# programmer-smd.net
KiCad netlist of a schematic drawn in EAGLE
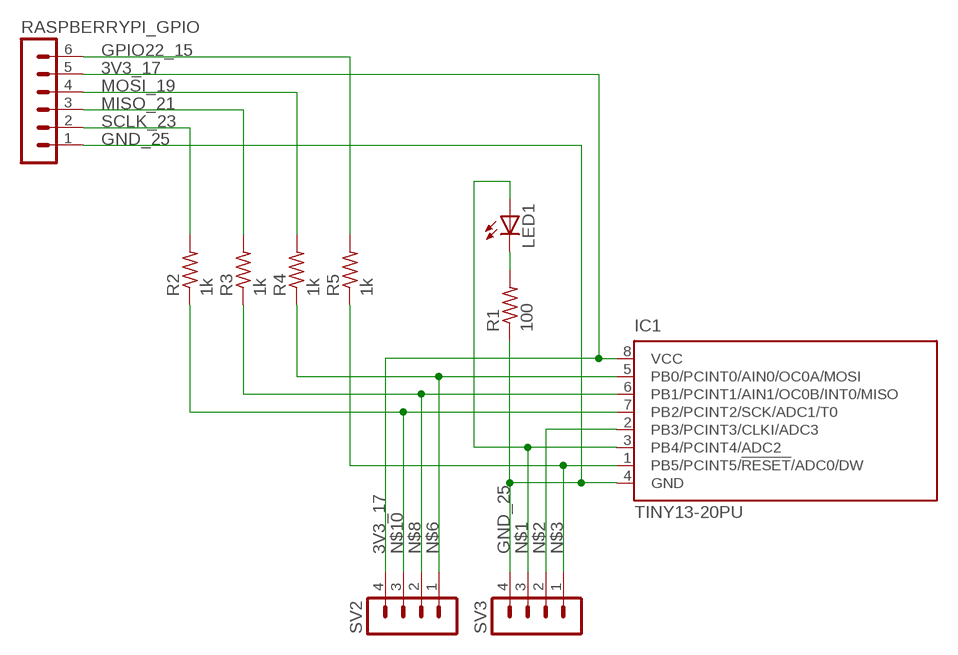
[diagram p0: schematic, sheet 1]

(export (version "E")
  (design (tool "Eeschema 10.0.6"))
  (components
    (comp (ref "IC1")
      (value "TINY13-20PU")
      (footprint "eagle-import:DIL08")
      (fields (field (name "MPN") "ATTINY13-20PU"))
      (libsource (lib "eagle-import") (part "TINY13PU-20"))
    )
    (comp (ref "LED1")
      (value "LEDCHIP-LED0805")
      (footprint "eagle-import:CHIP-LED0805")
      (libsource (lib "eagle-import") (part "LEDCHIP-LED0805"))
    )
    (comp (ref "R1")
      (value "100")
      (footprint "eagle-import:M0805")
      (libsource (lib "eagle-import") (part "R-US_M0805"))
    )
    (comp (ref "R2")
      (value "1k")
      (footprint "eagle-import:M0805")
      (libsource (lib "eagle-import") (part "R-US_M0805"))
    )
    (comp (ref "R3")
      (value "1k")
      (footprint "eagle-import:M0805")
      (libsource (lib "eagle-import") (part "R-US_M0805"))
    )
    (comp (ref "R4")
      (value "1k")
      (footprint "eagle-import:M0805")
      (libsource (lib "eagle-import") (part "R-US_M0805"))
    )
    (comp (ref "R5")
      (value "1k")
      (footprint "eagle-import:M0805")
      (libsource (lib "eagle-import") (part "R-US_M0805"))
    )
    (comp (ref "RASPBERRYPI_GPIO")
      (value "MA06-1")
      (footprint "eagle-import:MA06-1")
      (libsource (lib "eagle-import") (part "MA06-1"))
    )
    (comp (ref "SV2")
      (value "MA04-1")
      (footprint "eagle-import:MA04-1")
      (libsource (lib "eagle-import") (part "MA04-1"))
    )
    (comp (ref "SV3")
      (value "MA04-1")
      (footprint "eagle-import:MA04-1")
      (libsource (lib "eagle-import") (part "MA04-1"))
    )
  )
  (nets
    (net (code "1") (name "/3V3_17") (class "Default")
      (node (ref "IC1") (pin "8") (pinfunction "VCC_8") (pintype "power_in"))
      (node (ref "RASPBERRYPI_GPIO") (pin "5") (pinfunction "5_5") (pintype "passive"))
      (node (ref "SV2") (pin "4") (pinfunction "4_4") (pintype "passive"))
    )
    (net (code "2") (name "/GND_25") (class "Default")
      (node (ref "IC1") (pin "4") (pinfunction "GND_4") (pintype "power_in"))
      (node (ref "R1") (pin "1") (pinfunction "1_1") (pintype "passive"))
      (node (ref "RASPBERRYPI_GPIO") (pin "1") (pinfunction "1_1") (pintype "passive"))
      (node (ref "SV3") (pin "4") (pinfunction "4_4") (pintype "passive"))
    )
    (net (code "3") (name "/GPIO22_15") (class "Default")
      (node (ref "R5") (pin "2") (pinfunction "2_2") (pintype "passive"))
      (node (ref "RASPBERRYPI_GPIO") (pin "6") (pinfunction "6_6") (pintype "passive"))
    )
    (net (code "4") (name "/MISO_21") (class "Default")
      (node (ref "R3") (pin "2") (pinfunction "2_2") (pintype "passive"))
      (node (ref "RASPBERRYPI_GPIO") (pin "3") (pinfunction "3_3") (pintype "passive"))
    )
    (net (code "5") (name "/MOSI_19") (class "Default")
      (node (ref "R4") (pin "2") (pinfunction "2_2") (pintype "passive"))
      (node (ref "RASPBERRYPI_GPIO") (pin "4") (pinfunction "4_4") (pintype "passive"))
    )
    (net (code "6") (name "/N$1") (class "Default")
      (node (ref "IC1") (pin "3") (pinfunction "PB4/PCINT4/ADC2_3") (pintype "bidirectional"))
      (node (ref "LED1") (pin "A") (pinfunction "A_A") (pintype "passive"))
      (node (ref "SV3") (pin "3") (pinfunction "3_3") (pintype "passive"))
    )
    (net (code "7") (name "/N$2") (class "Default")
      (node (ref "IC1") (pin "2") (pinfunction "PB3/PCINT3/CLKI/ADC3_2") (pintype "bidirectional"))
      (node (ref "SV3") (pin "2") (pinfunction "2_2") (pintype "passive"))
    )
    (net (code "8") (name "/N$3") (class "Default")
      (node (ref "IC1") (pin "1") (pinfunction "PB5/PCINT5/~{RESET}/ADC0/DW_1") (pintype "bidirectional"))
      (node (ref "R5") (pin "1") (pinfunction "1_1") (pintype "passive"))
      (node (ref "SV3") (pin "1") (pinfunction "1_1") (pintype "passive"))
    )
    (net (code "9") (name "/N$6") (class "Default")
      (node (ref "IC1") (pin "5") (pinfunction "PB0/PCINT0/AIN0/OC0A/MOSI_5") (pintype "bidirectional"))
      (node (ref "R4") (pin "1") (pinfunction "1_1") (pintype "passive"))
      (node (ref "SV2") (pin "1") (pinfunction "1_1") (pintype "passive"))
    )
    (net (code "10") (name "/N$8") (class "Default")
      (node (ref "IC1") (pin "6") (pinfunction "PB1/PCINT1/AIN1/OC0B/INT0/MISO_6") (pintype "bidirectional"))
      (node (ref "R3") (pin "1") (pinfunction "1_1") (pintype "passive"))
      (node (ref "SV2") (pin "2") (pinfunction "2_2") (pintype "passive"))
    )
    (net (code "11") (name "/N$10") (class "Default")
      (node (ref "IC1") (pin "7") (pinfunction "PB2/PCINT2/SCK/ADC1/T0_7") (pintype "bidirectional"))
      (node (ref "R2") (pin "1") (pinfunction "1_1") (pintype "passive"))
      (node (ref "SV2") (pin "3") (pinfunction "3_3") (pintype "passive"))
    )
    (net (code "12") (name "/SCLK_23") (class "Default")
      (node (ref "R2") (pin "2") (pinfunction "2_2") (pintype "passive"))
      (node (ref "RASPBERRYPI_GPIO") (pin "2") (pinfunction "2_2") (pintype "passive"))
    )
    (net (code "13") (name "Net-(LED1-PadC)") (class "Default")
      (node (ref "LED1") (pin "C") (pinfunction "C_C") (pintype "passive"))
      (node (ref "R1") (pin "2") (pinfunction "2_2") (pintype "passive"))
    )
  )
)
